# dual-encoding.net
KiCad netlist of a schematic drawn in EAGLE
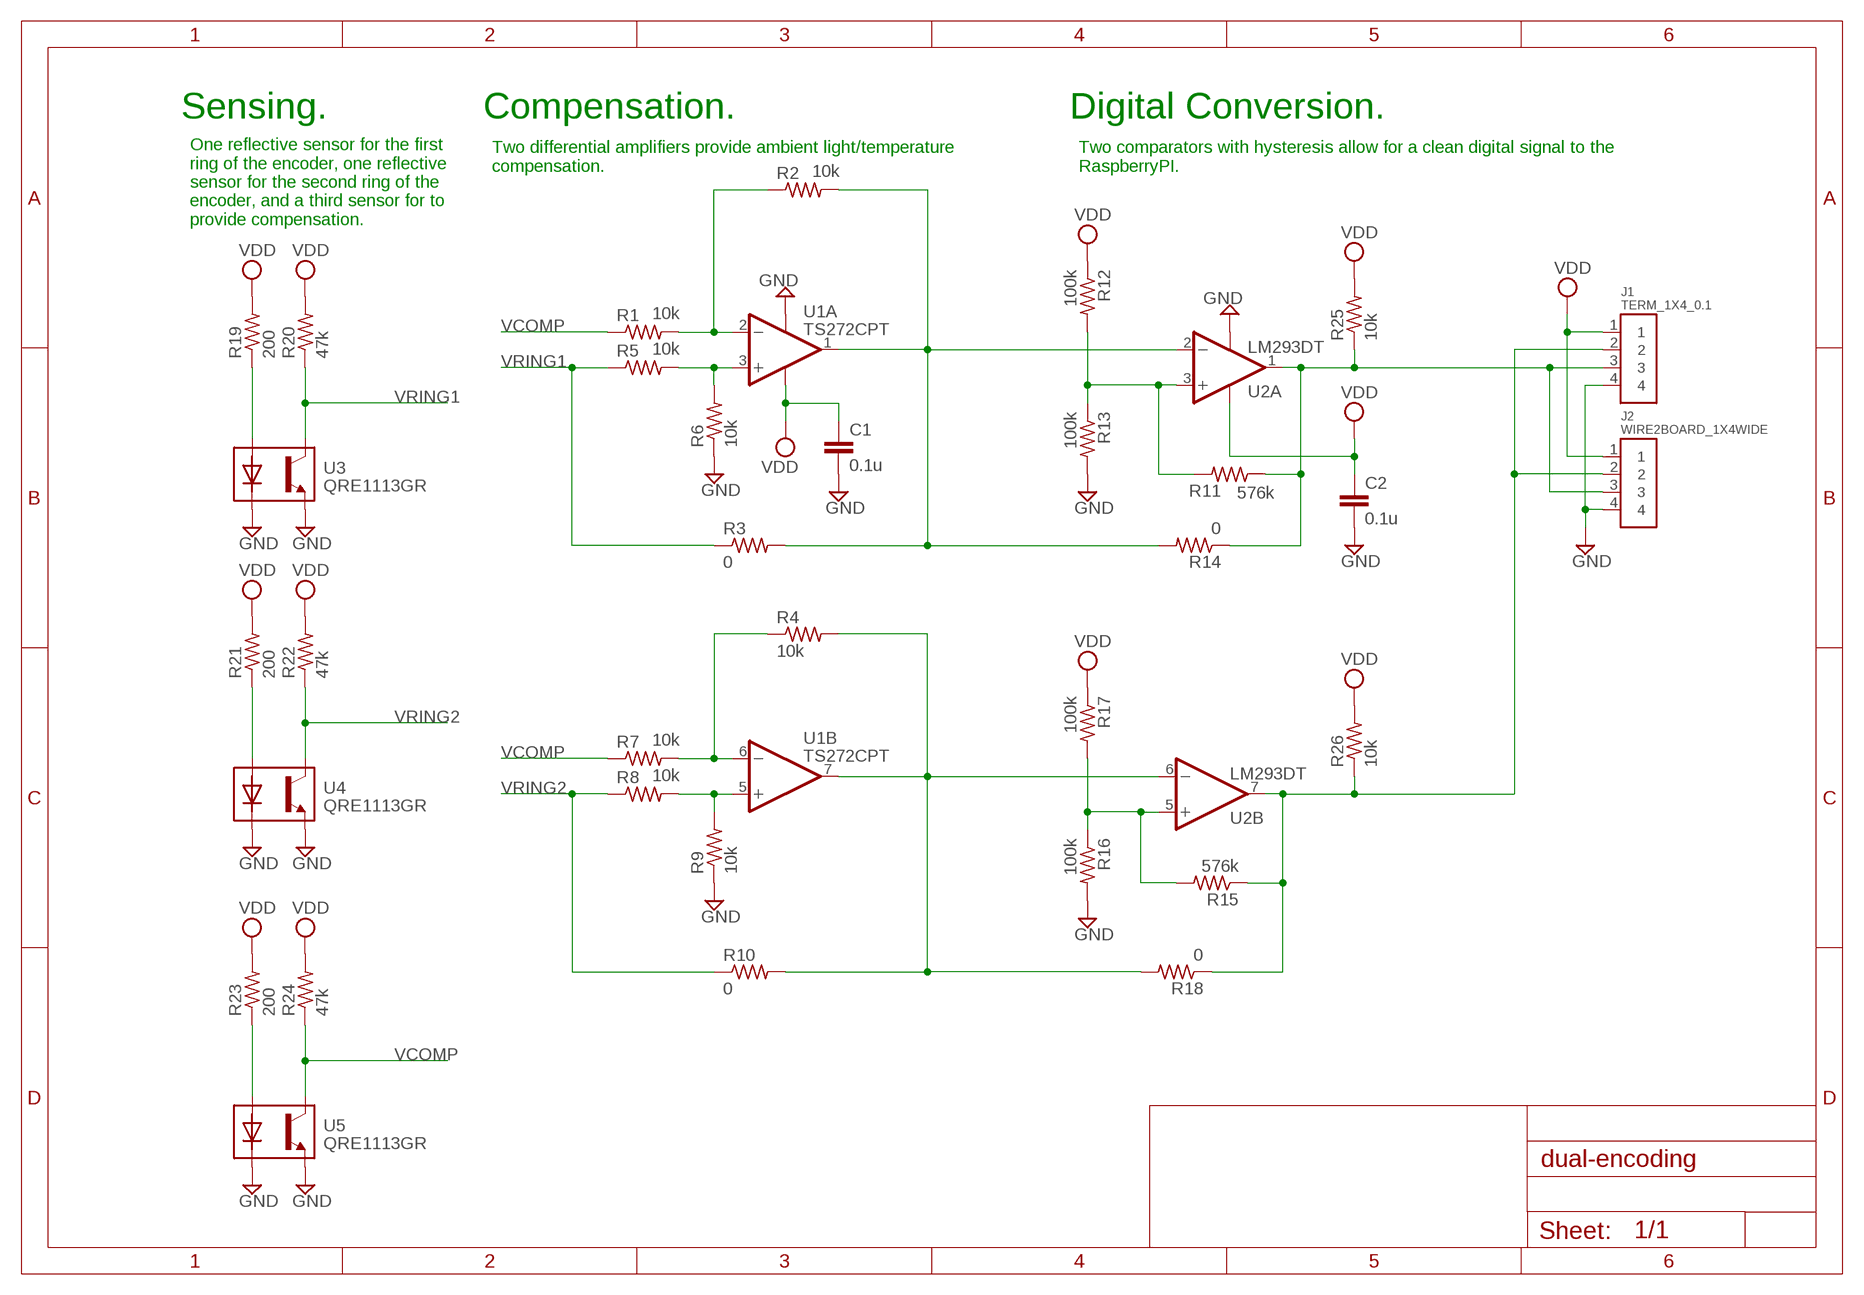
[diagram p0: schematic, sheet 1]

(export (version "E")
  (design (tool "Eeschema 10.0.6"))
  (components
    (comp (ref "C1")
      (value "0.1u")
      (footprint "eagle-import:C0805")
      (libsource (lib "eagle-import") (part "C0805"))
    )
    (comp (ref "C2")
      (value "0.1u")
      (footprint "eagle-import:C0805")
      (libsource (lib "eagle-import") (part "C0805"))
    )
    (comp (ref "J1")
      (value "TERM_1X4_0.1")
      (footprint "eagle-import:TERM_1X4_0.1")
      (libsource (lib "eagle-import") (part "TERM_1X4_0.1"))
    )
    (comp (ref "J2")
      (value "WIRE2BOARD_1X4WIDE")
      (footprint "eagle-import:WIRE2BOARD_1X4W")
      (libsource (lib "eagle-import") (part "WIRE2BOARD_1X4WIDE"))
    )
    (comp (ref "R1")
      (value "10k")
      (footprint "eagle-import:R0805")
      (libsource (lib "eagle-import") (part "R"))
    )
    (comp (ref "R2")
      (value "10k")
      (footprint "eagle-import:R0805")
      (libsource (lib "eagle-import") (part "R"))
    )
    (comp (ref "R3") (value "0") (footprint "eagle-import:R0805") (libsource (lib "eagle-import") (part "R")))
    (comp (ref "R4")
      (value "10k")
      (footprint "eagle-import:R0805")
      (libsource (lib "eagle-import") (part "R"))
    )
    (comp (ref "R5")
      (value "10k")
      (footprint "eagle-import:R0805")
      (libsource (lib "eagle-import") (part "R"))
    )
    (comp (ref "R6")
      (value "10k")
      (footprint "eagle-import:R0805")
      (libsource (lib "eagle-import") (part "R"))
    )
    (comp (ref "R7")
      (value "10k")
      (footprint "eagle-import:R0805")
      (libsource (lib "eagle-import") (part "R"))
    )
    (comp (ref "R8")
      (value "10k")
      (footprint "eagle-import:R0805")
      (libsource (lib "eagle-import") (part "R"))
    )
    (comp (ref "R9")
      (value "10k")
      (footprint "eagle-import:R0805")
      (libsource (lib "eagle-import") (part "R"))
    )
    (comp (ref "R10")
      (value "0")
      (footprint "eagle-import:R0805")
      (libsource (lib "eagle-import") (part "R"))
    )
    (comp (ref "R11")
      (value "576k")
      (footprint "eagle-import:R0805")
      (libsource (lib "eagle-import") (part "R"))
    )
    (comp (ref "R12")
      (value "100k")
      (footprint "eagle-import:R0805")
      (libsource (lib "eagle-import") (part "R"))
    )
    (comp (ref "R13")
      (value "100k")
      (footprint "eagle-import:R0805")
      (libsource (lib "eagle-import") (part "R"))
    )
    (comp (ref "R14")
      (value "0")
      (footprint "eagle-import:R0805")
      (libsource (lib "eagle-import") (part "R"))
    )
    (comp (ref "R15")
      (value "576k")
      (footprint "eagle-import:R0805")
      (libsource (lib "eagle-import") (part "R"))
    )
    (comp (ref "R16")
      (value "100k")
      (footprint "eagle-import:R0805")
      (libsource (lib "eagle-import") (part "R"))
    )
    (comp (ref "R17")
      (value "100k")
      (footprint "eagle-import:R0805")
      (libsource (lib "eagle-import") (part "R"))
    )
    (comp (ref "R18")
      (value "0")
      (footprint "eagle-import:R0805")
      (libsource (lib "eagle-import") (part "R"))
    )
    (comp (ref "R19")
      (value "200")
      (footprint "eagle-import:R0805")
      (libsource (lib "eagle-import") (part "R"))
    )
    (comp (ref "R20")
      (value "47k")
      (footprint "eagle-import:R0805")
      (libsource (lib "eagle-import") (part "R"))
    )
    (comp (ref "R21")
      (value "200")
      (footprint "eagle-import:R0805")
      (libsource (lib "eagle-import") (part "R"))
    )
    (comp (ref "R22")
      (value "47k")
      (footprint "eagle-import:R0805")
      (libsource (lib "eagle-import") (part "R"))
    )
    (comp (ref "R23")
      (value "200")
      (footprint "eagle-import:R0805")
      (libsource (lib "eagle-import") (part "R"))
    )
    (comp (ref "R24")
      (value "47k")
      (footprint "eagle-import:R0805")
      (libsource (lib "eagle-import") (part "R"))
    )
    (comp (ref "R25")
      (value "10k")
      (footprint "eagle-import:R0805")
      (libsource (lib "eagle-import") (part "R"))
    )
    (comp (ref "R26")
      (value "10k")
      (footprint "eagle-import:R0805")
      (libsource (lib "eagle-import") (part "R"))
    )
    (comp (ref "U1")
      (value "TS272CPT")
      (footprint "eagle-import:TSSOP8")
      (fields (field (name "DKPN") "497-8079-1-ND"))
      (libsource (lib "eagle-import") (part "TS272CPT"))
    )
    (comp (ref "U2")
      (value "LM293DT")
      (footprint "eagle-import:SOIC8")
      (fields (field (name "DKPN") "497-1566-1-ND"))
      (libsource (lib "eagle-import") (part "LM293DT"))
    )
    (comp (ref "U3")
      (value "QRE1113GR")
      (footprint "eagle-import:REFL")
      (libsource (lib "eagle-import") (part "QRE1113GR"))
    )
    (comp (ref "U4")
      (value "QRE1113GR")
      (footprint "eagle-import:REFL")
      (libsource (lib "eagle-import") (part "QRE1113GR"))
    )
    (comp (ref "U5")
      (value "QRE1113GR")
      (footprint "eagle-import:REFL")
      (libsource (lib "eagle-import") (part "QRE1113GR"))
    )
  )
  (nets
    (net (code "1") (name "/VCOMP") (class "Default")
      (node (ref "R1") (pin "1") (pinfunction "1_1") (pintype "passive"))
      (node (ref "R24") (pin "1") (pinfunction "1_1") (pintype "passive"))
      (node (ref "R7") (pin "1") (pinfunction "1_1") (pintype "passive"))
      (node (ref "U5") (pin "3") (pinfunction "C_3") (pintype "passive"))
    )
    (net (code "2") (name "/VRING1") (class "Default")
      (node (ref "R20") (pin "1") (pinfunction "1_1") (pintype "passive"))
      (node (ref "R3") (pin "1") (pinfunction "1_1") (pintype "passive"))
      (node (ref "R5") (pin "1") (pinfunction "1_1") (pintype "passive"))
      (node (ref "U3") (pin "3") (pinfunction "C_3") (pintype "passive"))
    )
    (net (code "3") (name "/VRING2") (class "Default")
      (node (ref "R10") (pin "1") (pinfunction "1_1") (pintype "passive"))
      (node (ref "R22") (pin "1") (pinfunction "1_1") (pintype "passive"))
      (node (ref "R8") (pin "1") (pinfunction "1_1") (pintype "passive"))
      (node (ref "U4") (pin "3") (pinfunction "C_3") (pintype "passive"))
    )
    (net (code "4") (name "GND") (class "Default")
      (node (ref "C1") (pin "2") (pinfunction "2_2") (pintype "passive"))
      (node (ref "C2") (pin "2") (pinfunction "2_2") (pintype "passive"))
      (node (ref "J1") (pin "4") (pinfunction "4_4") (pintype "bidirectional"))
      (node (ref "J2") (pin "4") (pinfunction "4_4") (pintype "bidirectional"))
      (node (ref "R13") (pin "2") (pinfunction "2_2") (pintype "passive"))
      (node (ref "R16") (pin "2") (pinfunction "2_2") (pintype "passive"))
      (node (ref "R6") (pin "1") (pinfunction "1_1") (pintype "passive"))
      (node (ref "R9") (pin "1") (pinfunction "1_1") (pintype "passive"))
      (node (ref "U1") (pin "4") (pinfunction "V-_4") (pintype "power_in"))
      (node (ref "U2") (pin "4") (pinfunction "V-_4") (pintype "power_in"))
      (node (ref "U3") (pin "2") (pinfunction "DC_2") (pintype "passive"))
      (node (ref "U3") (pin "4") (pinfunction "E_4") (pintype "passive"))
      (node (ref "U4") (pin "2") (pinfunction "DC_2") (pintype "passive"))
      (node (ref "U4") (pin "4") (pinfunction "E_4") (pintype "passive"))
      (node (ref "U5") (pin "2") (pinfunction "DC_2") (pintype "passive"))
      (node (ref "U5") (pin "4") (pinfunction "E_4") (pintype "passive"))
    )
    (net (code "5") (name "Net-(U1A-+IN)") (class "Default")
      (node (ref "R5") (pin "2") (pinfunction "2_2") (pintype "passive"))
      (node (ref "R6") (pin "2") (pinfunction "2_2") (pintype "passive"))
      (node (ref "U1") (pin "3") (pinfunction "+IN_3") (pintype "input"))
    )
    (net (code "6") (name "Net-(U1A--IN)") (class "Default")
      (node (ref "R1") (pin "2") (pinfunction "2_2") (pintype "passive"))
      (node (ref "R2") (pin "1") (pinfunction "1_1") (pintype "passive"))
      (node (ref "U1") (pin "2") (pinfunction "-IN_2") (pintype "input"))
    )
    (net (code "7") (name "Net-(U1A-OUT)") (class "Default")
      (node (ref "R14") (pin "2") (pinfunction "2_2") (pintype "passive"))
      (node (ref "R2") (pin "2") (pinfunction "2_2") (pintype "passive"))
      (node (ref "R3") (pin "2") (pinfunction "2_2") (pintype "passive"))
      (node (ref "U1") (pin "1") (pinfunction "OUT_1") (pintype "output"))
      (node (ref "U2") (pin "2") (pinfunction "-IN_2") (pintype "input"))
    )
    (net (code "8") (name "Net-(U1B-+IN)") (class "Default")
      (node (ref "R8") (pin "2") (pinfunction "2_2") (pintype "passive"))
      (node (ref "R9") (pin "2") (pinfunction "2_2") (pintype "passive"))
      (node (ref "U1") (pin "5") (pinfunction "+IN_5") (pintype "input"))
    )
    (net (code "9") (name "Net-(U1B--IN)") (class "Default")
      (node (ref "R4") (pin "1") (pinfunction "1_1") (pintype "passive"))
      (node (ref "R7") (pin "2") (pinfunction "2_2") (pintype "passive"))
      (node (ref "U1") (pin "6") (pinfunction "-IN_6") (pintype "input"))
    )
    (net (code "10") (name "Net-(U1B-OUT)") (class "Default")
      (node (ref "R10") (pin "2") (pinfunction "2_2") (pintype "passive"))
      (node (ref "R18") (pin "2") (pinfunction "2_2") (pintype "passive"))
      (node (ref "R4") (pin "2") (pinfunction "2_2") (pintype "passive"))
      (node (ref "U1") (pin "7") (pinfunction "OUT_7") (pintype "output"))
      (node (ref "U2") (pin "6") (pinfunction "-IN_6") (pintype "input"))
    )
    (net (code "11") (name "Net-(U2A-+IN)") (class "Default")
      (node (ref "R11") (pin "2") (pinfunction "2_2") (pintype "passive"))
      (node (ref "R12") (pin "2") (pinfunction "2_2") (pintype "passive"))
      (node (ref "R13") (pin "1") (pinfunction "1_1") (pintype "passive"))
      (node (ref "U2") (pin "3") (pinfunction "+IN_3") (pintype "input"))
    )
    (net (code "12") (name "Net-(U2A-OUT)") (class "Default")
      (node (ref "J1") (pin "3") (pinfunction "3_3") (pintype "bidirectional"))
      (node (ref "J2") (pin "3") (pinfunction "3_3") (pintype "bidirectional"))
      (node (ref "R11") (pin "1") (pinfunction "1_1") (pintype "passive"))
      (node (ref "R14") (pin "1") (pinfunction "1_1") (pintype "passive"))
      (node (ref "R25") (pin "1") (pinfunction "1_1") (pintype "passive"))
      (node (ref "U2") (pin "1") (pinfunction "OUT_1") (pintype "output"))
    )
    (net (code "13") (name "Net-(U2B-+IN)") (class "Default")
      (node (ref "R15") (pin "2") (pinfunction "2_2") (pintype "passive"))
      (node (ref "R16") (pin "1") (pinfunction "1_1") (pintype "passive"))
      (node (ref "R17") (pin "2") (pinfunction "2_2") (pintype "passive"))
      (node (ref "U2") (pin "5") (pinfunction "+IN_5") (pintype "input"))
    )
    (net (code "14") (name "Net-(U2B-OUT)") (class "Default")
      (node (ref "J1") (pin "2") (pinfunction "2_2") (pintype "bidirectional"))
      (node (ref "J2") (pin "2") (pinfunction "2_2") (pintype "bidirectional"))
      (node (ref "R15") (pin "1") (pinfunction "1_1") (pintype "passive"))
      (node (ref "R18") (pin "1") (pinfunction "1_1") (pintype "passive"))
      (node (ref "R26") (pin "1") (pinfunction "1_1") (pintype "passive"))
      (node (ref "U2") (pin "7") (pinfunction "OUT_7") (pintype "output"))
    )
    (net (code "15") (name "Net-(U3-DA)") (class "Default")
      (node (ref "R19") (pin "1") (pinfunction "1_1") (pintype "passive"))
      (node (ref "U3") (pin "1") (pinfunction "DA_1") (pintype "passive"))
    )
    (net (code "16") (name "Net-(U4-DA)") (class "Default")
      (node (ref "R21") (pin "1") (pinfunction "1_1") (pintype "passive"))
      (node (ref "U4") (pin "1") (pinfunction "DA_1") (pintype "passive"))
    )
    (net (code "17") (name "Net-(U5-DA)") (class "Default")
      (node (ref "R23") (pin "1") (pinfunction "1_1") (pintype "passive"))
      (node (ref "U5") (pin "1") (pinfunction "DA_1") (pintype "passive"))
    )
    (net (code "18") (name "VDD") (class "Default")
      (node (ref "C1") (pin "1") (pinfunction "1_1") (pintype "passive"))
      (node (ref "C2") (pin "1") (pinfunction "1_1") (pintype "passive"))
      (node (ref "J1") (pin "1") (pinfunction "1_1") (pintype "bidirectional"))
      (node (ref "J2") (pin "1") (pinfunction "1_1") (pintype "bidirectional"))
      (node (ref "R12") (pin "1") (pinfunction "1_1") (pintype "passive"))
      (node (ref "R17") (pin "1") (pinfunction "1_1") (pintype "passive"))
      (node (ref "R19") (pin "2") (pinfunction "2_2") (pintype "passive"))
      (node (ref "R20") (pin "2") (pinfunction "2_2") (pintype "passive"))
      (node (ref "R21") (pin "2") (pinfunction "2_2") (pintype "passive"))
      (node (ref "R22") (pin "2") (pinfunction "2_2") (pintype "passive"))
      (node (ref "R23") (pin "2") (pinfunction "2_2") (pintype "passive"))
      (node (ref "R24") (pin "2") (pinfunction "2_2") (pintype "passive"))
      (node (ref "R25") (pin "2") (pinfunction "2_2") (pintype "passive"))
      (node (ref "R26") (pin "2") (pinfunction "2_2") (pintype "passive"))
      (node (ref "U1") (pin "8") (pinfunction "V+_8") (pintype "power_in"))
      (node (ref "U2") (pin "8") (pinfunction "V+_8") (pintype "power_in"))
    )
  )
)
